# LDConnector_v2.net
KiCad netlist of a schematic drawn in EAGLE
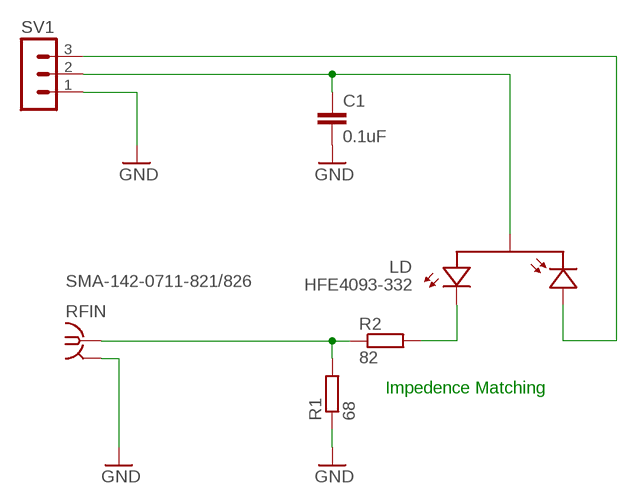
[diagram p0: schematic, sheet 1]

(export (version "E")
  (design (tool "Eeschema 10.0.6"))
  (components
    (comp (ref "C1")
      (value "0.1uF")
      (footprint "eagle-import:C0603")
      (libsource (lib "eagle-import") (part "C-EUC0603"))
    )
    (comp (ref "LD")
      (value "HFE4093-332")
      (footprint "eagle-import:HFE4093-332-EDGE")
      (libsource (lib "eagle-import") (part "HFE4093-332"))
    )
    (comp (ref "R1")
      (value "68")
      (footprint "eagle-import:R0603")
      (libsource (lib "eagle-import") (part "R-EU_R0603"))
    )
    (comp (ref "R2")
      (value "82")
      (footprint "eagle-import:R0603")
      (libsource (lib "eagle-import") (part "R-EU_R0603"))
    )
    (comp (ref "RFIN")
      (value "SMA-142-0711-821/826")
      (footprint "eagle-import:J502-ND-142-0711-821_826")
      (fields (field (name "MF") "JOHNSON COMPONENTS") (field (name "MPN") "142-0711-821"))
      (libsource (lib "eagle-import") (part "SMA-142-0711-821/826"))
    )
    (comp (ref "SV1")
      (value "MA03-1")
      (footprint "eagle-import:MA03-1")
      (libsource (lib "eagle-import") (part "MA03-1"))
    )
  )
  (nets
    (net (code "1") (name "GND") (class "Default")
      (node (ref "C1") (pin "2") (pinfunction "2_2") (pintype "passive"))
      (node (ref "R1") (pin "1") (pinfunction "1_1") (pintype "passive"))
      (node (ref "RFIN") (pin "G@1") (pinfunction "2_G@1") (pintype "passive"))
      (node (ref "RFIN") (pin "G@2") (pinfunction "2_G@2") (pintype "passive"))
      (node (ref "RFIN") (pin "G@3") (pinfunction "2_G@3") (pintype "passive"))
      (node (ref "RFIN") (pin "G@4") (pinfunction "2_G@4") (pintype "passive"))
      (node (ref "SV1") (pin "1") (pinfunction "1_1") (pintype "passive"))
    )
    (net (code "2") (name "Net-(LD-LDA-PDC)") (class "Default")
      (node (ref "C1") (pin "1") (pinfunction "1_1") (pintype "passive"))
      (node (ref "LD") (pin "2-PD-CATHODE-LD-ANODE") (pinfunction "LDA-PDC_2-PD-CATHODE-LD-ANODE") (pintype "passive"))
      (node (ref "SV1") (pin "2") (pinfunction "2_2") (pintype "passive"))
    )
    (net (code "3") (name "Net-(LD-LDC)") (class "Default")
      (node (ref "LD") (pin "1-LD-CATHODE") (pinfunction "LDC_1-LD-CATHODE") (pintype "passive"))
      (node (ref "R2") (pin "2") (pinfunction "2_2") (pintype "passive"))
    )
    (net (code "4") (name "Net-(LD-PDA)") (class "Default")
      (node (ref "LD") (pin "3-PD-ANODE") (pinfunction "PDA_3-PD-ANODE") (pintype "passive"))
      (node (ref "SV1") (pin "3") (pinfunction "3_3") (pintype "passive"))
    )
    (net (code "5") (name "Net-(R1-Pad2)") (class "Default")
      (node (ref "R1") (pin "2") (pinfunction "2_2") (pintype "passive"))
      (node (ref "R2") (pin "1") (pinfunction "1_1") (pintype "passive"))
      (node (ref "RFIN") (pin "1") (pinfunction "1_1") (pintype "passive"))
    )
  )
)
